# SIM868-ng.net
KiCad netlist of a schematic drawn in EAGLE
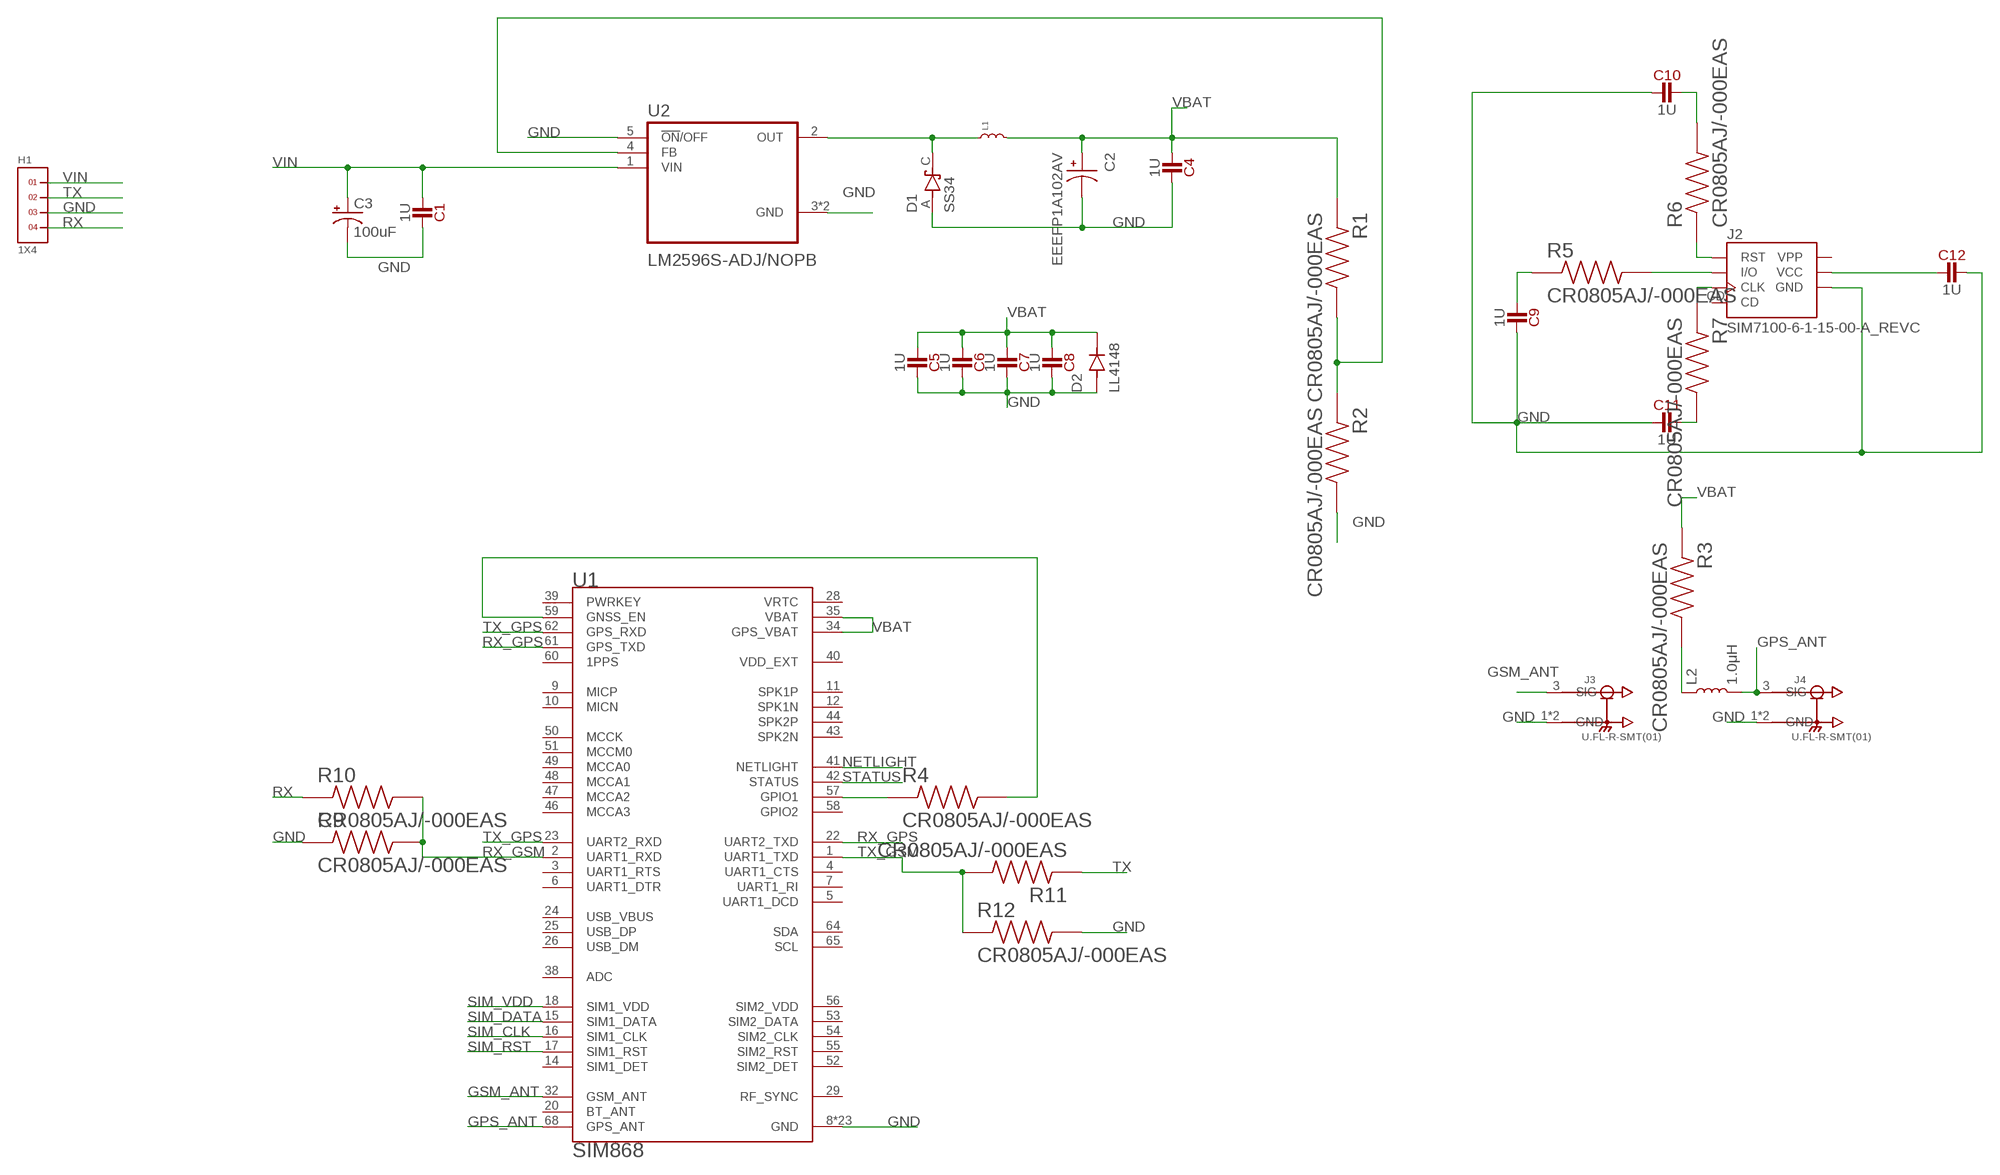
[diagram p0: schematic, sheet 1]

(export (version "E")
  (design (tool "Eeschema 10.0.6"))
  (components
    (comp (ref "C1")
      (value "1U")
      (footprint "eagle-import:C-0805")
      (libsource (lib "eagle-import") (part "?1U"))
    )
    (comp (ref "C2")
      (value "EEEFP1A102AV")
      (footprint "eagle-import:CAP_EEEFP1A102AV")
      (fields (field (name "MF") "Panasonic") (field (name "MP") "EEE-FP1A102AV"))
      (libsource (lib "eagle-import") (part "EEEFP1A102AV"))
    )
    (comp (ref "C3")
      (value "100uF")
      (footprint "eagle-import:EIA3528")
      (libsource (lib "eagle-import") (part "100UF-POLAR-EIA3528-10V-20%(TANT)"))
    )
    (comp (ref "C4")
      (value "1U")
      (footprint "eagle-import:C-0805")
      (libsource (lib "eagle-import") (part "?1U"))
    )
    (comp (ref "C5")
      (value "1U")
      (footprint "eagle-import:C-0805")
      (libsource (lib "eagle-import") (part "?1U"))
    )
    (comp (ref "C6")
      (value "1U")
      (footprint "eagle-import:C-0805")
      (libsource (lib "eagle-import") (part "?1U"))
    )
    (comp (ref "C7")
      (value "1U")
      (footprint "eagle-import:C-0805")
      (libsource (lib "eagle-import") (part "?1U"))
    )
    (comp (ref "C8")
      (value "1U")
      (footprint "eagle-import:C-0805")
      (libsource (lib "eagle-import") (part "?1U"))
    )
    (comp (ref "C9")
      (value "1U")
      (footprint "eagle-import:C-0805")
      (libsource (lib "eagle-import") (part "?1U"))
    )
    (comp (ref "C10")
      (value "1U")
      (footprint "eagle-import:C-0805")
      (libsource (lib "eagle-import") (part "?1U"))
    )
    (comp (ref "C11")
      (value "1U")
      (footprint "eagle-import:C-0805")
      (libsource (lib "eagle-import") (part "?1U"))
    )
    (comp (ref "C12")
      (value "1U")
      (footprint "eagle-import:C-0805")
      (libsource (lib "eagle-import") (part "?1U"))
    )
    (comp (ref "D1")
      (value "SS34")
      (footprint "eagle-import:DIOM7959X265N")
      (fields (field (name "MF") "ON Semiconductor"))
      (libsource (lib "eagle-import") (part "SS34"))
    )
    (comp (ref "D2")
      (value "LL4148")
      (footprint "eagle-import:DIO_LL4148")
      (fields (field (name "MF") "ON"))
      (libsource (lib "eagle-import") (part "LL4148"))
    )
    (comp (ref "H1")
      (value "1X4")
      (footprint "eagle-import:1X4")
      (libsource (lib "eagle-import") (part "1X4"))
    )
    (comp (ref "J2")
      (value "SIM7100-6-1-15-00-A_REVC")
      (footprint "eagle-import:GCT_SIM7100-6-1-15-00-A_REVC")
      (fields (field (name "MF") "Global Connector Technology") (field (name "MP") "SIM7100-6-1-15-00-A"))
      (libsource (lib "eagle-import") (part "SIM7100-6-1-15-00-A_REVC"))
    )
    (comp (ref "J3")
      (value "U.FL-R-SMT(01)")
      (footprint "eagle-import:HRS_U.FL-R-SMT(01)")
      (fields (field (name "MF") "Hirose Electric Co Ltd"))
      (libsource (lib "eagle-import") (part "U.FL-R-SMT(01)"))
    )
    (comp (ref "J4")
      (value "U.FL-R-SMT(01)")
      (footprint "eagle-import:HRS_U.FL-R-SMT(01)")
      (fields (field (name "MF") "Hirose Electric Co Ltd"))
      (libsource (lib "eagle-import") (part "U.FL-R-SMT(01)"))
    )
    (comp (ref "L1")
      (value "INDUCTOR.XAL1010")
      (footprint "eagle-import:XAL1010")
      (libsource (lib "eagle-import") (part "INDUCTOR.XAL1010"))
    )
    (comp (ref "L2")
      (value "1.0μH")
      (footprint "eagle-import:0805-WIDE")
      (libsource (lib "eagle-import") (part "1.0μH-0805_WIDE-1.0μH-1.45A-0.106OHM-1.0MM_H"))
    )
    (comp (ref "R1")
      (value "CR0805AJ/-000EAS")
      (footprint "eagle-import:RESC2012X60N")
      (fields (field (name "MF") "Bourns"))
      (libsource (lib "eagle-import") (part "CR0805AJ/-000EAS"))
    )
    (comp (ref "R2")
      (value "CR0805AJ/-000EAS")
      (footprint "eagle-import:RESC2012X60N")
      (fields (field (name "MF") "Bourns"))
      (libsource (lib "eagle-import") (part "CR0805AJ/-000EAS"))
    )
    (comp (ref "R3")
      (value "CR0805AJ/-000EAS")
      (footprint "eagle-import:RESC2012X60N")
      (fields (field (name "MF") "Bourns"))
      (libsource (lib "eagle-import") (part "CR0805AJ/-000EAS"))
    )
    (comp (ref "R4")
      (value "CR0805AJ/-000EAS")
      (footprint "eagle-import:RESC2012X60N")
      (fields (field (name "MF") "Bourns"))
      (libsource (lib "eagle-import") (part "CR0805AJ/-000EAS"))
    )
    (comp (ref "R5")
      (value "CR0805AJ/-000EAS")
      (footprint "eagle-import:RESC2012X60N")
      (fields (field (name "MF") "Bourns"))
      (libsource (lib "eagle-import") (part "CR0805AJ/-000EAS"))
    )
    (comp (ref "R6")
      (value "CR0805AJ/-000EAS")
      (footprint "eagle-import:RESC2012X60N")
      (fields (field (name "MF") "Bourns"))
      (libsource (lib "eagle-import") (part "CR0805AJ/-000EAS"))
    )
    (comp (ref "R7")
      (value "CR0805AJ/-000EAS")
      (footprint "eagle-import:RESC2012X60N")
      (fields (field (name "MF") "Bourns"))
      (libsource (lib "eagle-import") (part "CR0805AJ/-000EAS"))
    )
    (comp (ref "R9")
      (value "CR0805AJ/-000EAS")
      (footprint "eagle-import:RESC2012X60N")
      (fields (field (name "MF") "Bourns"))
      (libsource (lib "eagle-import") (part "CR0805AJ/-000EAS"))
    )
    (comp (ref "R10")
      (value "CR0805AJ/-000EAS")
      (footprint "eagle-import:RESC2012X60N")
      (fields (field (name "MF") "Bourns"))
      (libsource (lib "eagle-import") (part "CR0805AJ/-000EAS"))
    )
    (comp (ref "R11")
      (value "CR0805AJ/-000EAS")
      (footprint "eagle-import:RESC2012X60N")
      (fields (field (name "MF") "Bourns"))
      (libsource (lib "eagle-import") (part "CR0805AJ/-000EAS"))
    )
    (comp (ref "R12")
      (value "CR0805AJ/-000EAS")
      (footprint "eagle-import:RESC2012X60N")
      (fields (field (name "MF") "Bourns"))
      (libsource (lib "eagle-import") (part "CR0805AJ/-000EAS"))
    )
    (comp (ref "U1")
      (value "SIM868")
      (footprint "eagle-import:XCVR_SIM868")
      (fields (field (name "MF") "MikroElektronika"))
      (libsource (lib "eagle-import") (part "SIM868"))
    )
    (comp (ref "U2")
      (value "LM2596S-ADJ/NOPB")
      (footprint "eagle-import:VREG_LM2596S-ADJ_NOPB")
      (fields (field (name "MF") "Texas Instruments"))
      (libsource (lib "eagle-import") (part "LM2596S-ADJ/NOPB"))
    )
  )
  (nets
    (net (code "1") (name "/GND") (class "Default")
      (node (ref "C1") (pin "2") (pinfunction "2_2") (pintype "passive"))
      (node (ref "C10") (pin "1") (pinfunction "1_1") (pintype "passive"))
      (node (ref "C11") (pin "1") (pinfunction "1_1") (pintype "passive"))
      (node (ref "C12") (pin "2") (pinfunction "2_2") (pintype "passive"))
      (node (ref "C2") (pin "2") (pinfunction "2_2") (pintype "passive"))
      (node (ref "C3") (pin "C") (pinfunction "-_C") (pintype "passive"))
      (node (ref "C4") (pin "2") (pinfunction "2_2") (pintype "passive"))
      (node (ref "C5") (pin "2") (pinfunction "2_2") (pintype "passive"))
      (node (ref "C6") (pin "2") (pinfunction "2_2") (pintype "passive"))
      (node (ref "C7") (pin "2") (pinfunction "2_2") (pintype "passive"))
      (node (ref "C8") (pin "2") (pinfunction "2_2") (pintype "passive"))
      (node (ref "C9") (pin "2") (pinfunction "2_2") (pintype "passive"))
      (node (ref "D1") (pin "A") (pinfunction "A_A") (pintype "passive"))
      (node (ref "D2") (pin "A") (pinfunction "A_A") (pintype "passive"))
      (node (ref "H1") (pin "3") (pinfunction "3_3") (pintype "bidirectional"))
      (node (ref "J2") (pin "C5") (pinfunction "GND_C5") (pintype "power_in"))
      (node (ref "J3") (pin "1") (pinfunction "GND_1") (pintype "passive"))
      (node (ref "J3") (pin "2") (pinfunction "GND_2") (pintype "passive"))
      (node (ref "J4") (pin "1") (pinfunction "GND_1") (pintype "passive"))
      (node (ref "J4") (pin "2") (pinfunction "GND_2") (pintype "passive"))
      (node (ref "R12") (pin "2") (pinfunction "2_2") (pintype "passive"))
      (node (ref "R2") (pin "2") (pinfunction "2_2") (pintype "passive"))
      (node (ref "R9") (pin "1") (pinfunction "1_1") (pintype "passive"))
      (node (ref "U1") (pin "13") (pinfunction "GND_13") (pintype "power_in"))
      (node (ref "U1") (pin "19") (pinfunction "GND_19") (pintype "power_in"))
      (node (ref "U1") (pin "21") (pinfunction "GND_21") (pintype "power_in"))
      (node (ref "U1") (pin "27") (pinfunction "GND_27") (pintype "power_in"))
      (node (ref "U1") (pin "30") (pinfunction "GND_30") (pintype "power_in"))
      (node (ref "U1") (pin "31") (pinfunction "GND_31") (pintype "power_in"))
      (node (ref "U1") (pin "33") (pinfunction "GND_33") (pintype "power_in"))
      (node (ref "U1") (pin "36") (pinfunction "GND_36") (pintype "power_in"))
      (node (ref "U1") (pin "37") (pinfunction "GND_37") (pintype "power_in"))
      (node (ref "U1") (pin "45") (pinfunction "GND_45") (pintype "power_in"))
      (node (ref "U1") (pin "63") (pinfunction "GND_63") (pintype "power_in"))
      (node (ref "U1") (pin "66") (pinfunction "GND_66") (pintype "power_in"))
      (node (ref "U1") (pin "67") (pinfunction "GND_67") (pintype "power_in"))
      (node (ref "U1") (pin "69") (pinfunction "GND_69") (pintype "power_in"))
      (node (ref "U1") (pin "70") (pinfunction "GND_70") (pintype "power_in"))
      (node (ref "U1") (pin "71") (pinfunction "GND_71") (pintype "power_in"))
      (node (ref "U1") (pin "72") (pinfunction "GND_72") (pintype "power_in"))
      (node (ref "U1") (pin "73") (pinfunction "GND_73") (pintype "power_in"))
      (node (ref "U1") (pin "74") (pinfunction "GND_74") (pintype "power_in"))
      (node (ref "U1") (pin "75") (pinfunction "GND_75") (pintype "power_in"))
      (node (ref "U1") (pin "76") (pinfunction "GND_76") (pintype "power_in"))
      (node (ref "U1") (pin "77") (pinfunction "GND_77") (pintype "power_in"))
      (node (ref "U1") (pin "8") (pinfunction "GND_8") (pintype "power_in"))
      (node (ref "U2") (pin "3") (pinfunction "GND_3") (pintype "power_in"))
      (node (ref "U2") (pin "5") (pinfunction "~{ON}/OFF_5") (pintype "input"))
      (node (ref "U2") (pin "6") (pinfunction "GND_6") (pintype "power_in"))
    )
    (net (code "2") (name "/GPS_ANT") (class "Default")
      (node (ref "J4") (pin "3") (pinfunction "SIG_3") (pintype "passive"))
      (node (ref "L2") (pin "2") (pinfunction "2_2") (pintype "passive"))
      (node (ref "U1") (pin "68") (pinfunction "GPS_ANT_68") (pintype "input"))
    )
    (net (code "3") (name "/GSM_ANT") (class "Default")
      (node (ref "J3") (pin "3") (pinfunction "SIG_3") (pintype "passive"))
      (node (ref "U1") (pin "32") (pinfunction "GSM_ANT_32") (pintype "bidirectional"))
    )
    (net (code "4") (name "/NETLIGHT") (class "Default")
      (node (ref "U1") (pin "41") (pinfunction "NETLIGHT_41") (pintype "output"))
    )
    (net (code "5") (name "/RX") (class "Default")
      (node (ref "H1") (pin "4") (pinfunction "4_4") (pintype "bidirectional"))
      (node (ref "R10") (pin "1") (pinfunction "1_1") (pintype "passive"))
    )
    (net (code "6") (name "/RX_GPS") (class "Default")
      (node (ref "U1") (pin "22") (pinfunction "UART2_TXD_22") (pintype "output"))
      (node (ref "U1") (pin "61") (pinfunction "GPS_TXD_61") (pintype "output"))
    )
    (net (code "7") (name "/RX_GSM") (class "Default")
      (node (ref "R10") (pin "2") (pinfunction "2_2") (pintype "passive"))
      (node (ref "R9") (pin "2") (pinfunction "2_2") (pintype "passive"))
      (node (ref "U1") (pin "2") (pinfunction "UART1_RXD_2") (pintype "input"))
    )
    (net (code "8") (name "/SIM_CLK") (class "Default")
      (node (ref "U1") (pin "16") (pinfunction "SIM1_CLK_16") (pintype "output"))
    )
    (net (code "9") (name "/SIM_DATA") (class "Default")
      (node (ref "U1") (pin "15") (pinfunction "SIM1_DATA_15") (pintype "bidirectional"))
    )
    (net (code "10") (name "/SIM_RST") (class "Default")
      (node (ref "U1") (pin "17") (pinfunction "SIM1_RST_17") (pintype "output"))
    )
    (net (code "11") (name "/SIM_VDD") (class "Default")
      (node (ref "U1") (pin "18") (pinfunction "SIM1_VDD_18") (pintype "output"))
    )
    (net (code "12") (name "/STATUS") (class "Default")
      (node (ref "U1") (pin "42") (pinfunction "STATUS_42") (pintype "output"))
    )
    (net (code "13") (name "/TX") (class "Default")
      (node (ref "H1") (pin "2") (pinfunction "2_2") (pintype "bidirectional"))
      (node (ref "R11") (pin "1") (pinfunction "1_1") (pintype "passive"))
    )
    (net (code "14") (name "/TX_GPS") (class "Default")
      (node (ref "U1") (pin "23") (pinfunction "UART2_RXD_23") (pintype "input"))
      (node (ref "U1") (pin "62") (pinfunction "GPS_RXD_62") (pintype "input"))
    )
    (net (code "15") (name "/TX_GSM") (class "Default")
      (node (ref "R11") (pin "2") (pinfunction "2_2") (pintype "passive"))
      (node (ref "R12") (pin "1") (pinfunction "1_1") (pintype "passive"))
      (node (ref "U1") (pin "1") (pinfunction "UART1_TXD_1") (pintype "output"))
    )
    (net (code "16") (name "/VBAT") (class "Default")
      (node (ref "C2") (pin "1") (pinfunction "1_1") (pintype "passive"))
      (node (ref "C4") (pin "1") (pinfunction "1_1") (pintype "passive"))
      (node (ref "C5") (pin "1") (pinfunction "1_1") (pintype "passive"))
      (node (ref "C6") (pin "1") (pinfunction "1_1") (pintype "passive"))
      (node (ref "C7") (pin "1") (pinfunction "1_1") (pintype "passive"))
      (node (ref "C8") (pin "1") (pinfunction "1_1") (pintype "passive"))
      (node (ref "D2") (pin "C") (pinfunction "C_C") (pintype "passive"))
      (node (ref "L1") (pin "P$2") (pinfunction "2_P$2") (pintype "passive"))
      (node (ref "R1") (pin "1") (pinfunction "1_1") (pintype "passive"))
      (node (ref "R3") (pin "1") (pinfunction "1_1") (pintype "passive"))
      (node (ref "U1") (pin "34") (pinfunction "GPS_VBAT_34") (pintype "power_in"))
      (node (ref "U1") (pin "35") (pinfunction "VBAT_35") (pintype "power_in"))
    )
    (net (code "17") (name "/VIN") (class "Default")
      (node (ref "C1") (pin "1") (pinfunction "1_1") (pintype "passive"))
      (node (ref "C3") (pin "A") (pinfunction "+_A") (pintype "passive"))
      (node (ref "H1") (pin "1") (pinfunction "1_1") (pintype "bidirectional"))
      (node (ref "U2") (pin "1") (pinfunction "VIN_1") (pintype "input"))
    )
    (net (code "18") (name "/VPP") (class "Default")
      (node (ref "J2") (pin "C6") (pinfunction "VPP_C6") (pintype "power_in"))
    )
    (net (code "19") (name "/VRTC") (class "Default")
      (node (ref "U1") (pin "28") (pinfunction "VRTC_28") (pintype "power_in"))
    )
    (net (code "20") (name "Net-(C9-Pad1)") (class "Default")
      (node (ref "C9") (pin "1") (pinfunction "1_1") (pintype "passive"))
      (node (ref "R5") (pin "1") (pinfunction "1_1") (pintype "passive"))
    )
    (net (code "21") (name "Net-(C10-Pad2)") (class "Default")
      (node (ref "C10") (pin "2") (pinfunction "2_2") (pintype "passive"))
      (node (ref "R6") (pin "2") (pinfunction "2_2") (pintype "passive"))
    )
    (net (code "22") (name "Net-(C11-Pad2)") (class "Default")
      (node (ref "C11") (pin "2") (pinfunction "2_2") (pintype "passive"))
      (node (ref "R7") (pin "2") (pinfunction "2_2") (pintype "passive"))
    )
    (net (code "23") (name "Net-(D1-K)") (class "Default")
      (node (ref "D1") (pin "C") (pinfunction "K_C") (pintype "passive"))
      (node (ref "L1") (pin "P$1") (pinfunction "1_P$1") (pintype "passive"))
      (node (ref "U2") (pin "2") (pinfunction "OUT_2") (pintype "output"))
    )
    (net (code "24") (name "Net-(J2-CLK)") (class "Default")
      (node (ref "J2") (pin "C3") (pinfunction "CLK_C3") (pintype "bidirectional"))
      (node (ref "R7") (pin "1") (pinfunction "1_1") (pintype "passive"))
    )
    (net (code "25") (name "Net-(J2-I{slash}O)") (class "Default")
      (node (ref "J2") (pin "C7") (pinfunction "I/O_C7") (pintype "bidirectional"))
      (node (ref "R5") (pin "2") (pinfunction "2_2") (pintype "passive"))
    )
    (net (code "26") (name "Net-(J2-RST)") (class "Default")
      (node (ref "J2") (pin "C2") (pinfunction "RST_C2") (pintype "input"))
      (node (ref "R6") (pin "1") (pinfunction "1_1") (pintype "passive"))
    )
    (net (code "27") (name "Net-(J2-VCC)") (class "Default")
      (node (ref "C12") (pin "1") (pinfunction "1_1") (pintype "passive"))
      (node (ref "J2") (pin "C1") (pinfunction "VCC_C1") (pintype "power_in"))
    )
    (net (code "28") (name "Net-(L2-Pad1)") (class "Default")
      (node (ref "L2") (pin "1") (pinfunction "1_1") (pintype "passive"))
      (node (ref "R3") (pin "2") (pinfunction "2_2") (pintype "passive"))
    )
    (net (code "29") (name "Net-(U1-GNSS_EN)") (class "Default")
      (node (ref "R4") (pin "2") (pinfunction "2_2") (pintype "passive"))
      (node (ref "U1") (pin "59") (pinfunction "GNSS_EN_59") (pintype "input"))
    )
    (net (code "30") (name "Net-(U1-GPIO1)") (class "Default")
      (node (ref "R4") (pin "1") (pinfunction "1_1") (pintype "passive"))
      (node (ref "U1") (pin "57") (pinfunction "GPIO1_57") (pintype "bidirectional"))
    )
    (net (code "31") (name "Net-(U2-FB)") (class "Default")
      (node (ref "R1") (pin "2") (pinfunction "2_2") (pintype "passive"))
      (node (ref "R2") (pin "1") (pinfunction "1_1") (pintype "passive"))
      (node (ref "U2") (pin "4") (pinfunction "FB_4") (pintype "input"))
    )
    (net (code "32") (name "unconnected-(J2-PadCD)") (class "Default")
      (node (ref "J2") (pin "CD") (pinfunction "CD_CD") (pintype "passive"))
    )
    (net (code "33") (name "unconnected-(U1-1PPS-Pad60)") (class "Default")
      (node (ref "U1") (pin "60") (pinfunction "1PPS_60") (pintype "output"))
    )
    (net (code "34") (name "unconnected-(U1-ADC-Pad38)") (class "Default")
      (node (ref "U1") (pin "38") (pinfunction "ADC_38") (pintype "input"))
    )
    (net (code "35") (name "unconnected-(U1-BT_ANT-Pad20)") (class "Default")
      (node (ref "U1") (pin "20") (pinfunction "BT_ANT_20") (pintype "bidirectional"))
    )
    (net (code "36") (name "unconnected-(U1-GPIO2-Pad58)") (class "Default")
      (node (ref "U1") (pin "58") (pinfunction "GPIO2_58") (pintype "bidirectional"))
    )
    (net (code "37") (name "unconnected-(U1-MCCA0-Pad49)") (class "Default")
      (node (ref "U1") (pin "49") (pinfunction "MCCA0_49") (pintype "bidirectional"))
    )
    (net (code "38") (name "unconnected-(U1-MCCA1-Pad48)") (class "Default")
      (node (ref "U1") (pin "48") (pinfunction "MCCA1_48") (pintype "bidirectional"))
    )
    (net (code "39") (name "unconnected-(U1-MCCA2-Pad47)") (class "Default")
      (node (ref "U1") (pin "47") (pinfunction "MCCA2_47") (pintype "bidirectional"))
    )
    (net (code "40") (name "unconnected-(U1-MCCA3-Pad46)") (class "Default")
      (node (ref "U1") (pin "46") (pinfunction "MCCA3_46") (pintype "bidirectional"))
    )
    (net (code "41") (name "unconnected-(U1-MCCK-Pad50)") (class "Default")
      (node (ref "U1") (pin "50") (pinfunction "MCCK_50") (pintype "bidirectional"))
    )
    (net (code "42") (name "unconnected-(U1-MCCM0-Pad51)") (class "Default")
      (node (ref "U1") (pin "51") (pinfunction "MCCM0_51") (pintype "bidirectional"))
    )
    (net (code "43") (name "unconnected-(U1-MICN-Pad10)") (class "Default")
      (node (ref "U1") (pin "10") (pinfunction "MICN_10") (pintype "input"))
    )
    (net (code "44") (name "unconnected-(U1-MICP-Pad9)") (class "Default")
      (node (ref "U1") (pin "9") (pinfunction "MICP_9") (pintype "input"))
    )
    (net (code "45") (name "unconnected-(U1-PWRKEY-Pad39)") (class "Default")
      (node (ref "U1") (pin "39") (pinfunction "PWRKEY_39") (pintype "input"))
    )
    (net (code "46") (name "unconnected-(U1-RF_SYNC-Pad29)") (class "Default")
      (node (ref "U1") (pin "29") (pinfunction "RF_SYNC_29") (pintype "output"))
    )
    (net (code "47") (name "unconnected-(U1-SCL-Pad65)") (class "Default")
      (node (ref "U1") (pin "65") (pinfunction "SCL_65") (pintype "output"))
    )
    (net (code "48") (name "unconnected-(U1-SDA-Pad64)") (class "Default")
      (node (ref "U1") (pin "64") (pinfunction "SDA_64") (pintype "bidirectional"))
    )
    (net (code "49") (name "unconnected-(U1-SIM1_DET-Pad14)") (class "Default")
      (node (ref "U1") (pin "14") (pinfunction "SIM1_DET_14") (pintype "input"))
    )
    (net (code "50") (name "unconnected-(U1-SIM2_CLK-Pad54)") (class "Default")
      (node (ref "U1") (pin "54") (pinfunction "SIM2_CLK_54") (pintype "output"))
    )
    (net (code "51") (name "unconnected-(U1-SIM2_DATA-Pad53)") (class "Default")
      (node (ref "U1") (pin "53") (pinfunction "SIM2_DATA_53") (pintype "bidirectional"))
    )
    (net (code "52") (name "unconnected-(U1-SIM2_DET-Pad52)") (class "Default")
      (node (ref "U1") (pin "52") (pinfunction "SIM2_DET_52") (pintype "input"))
    )
    (net (code "53") (name "unconnected-(U1-SIM2_RST-Pad55)") (class "Default")
      (node (ref "U1") (pin "55") (pinfunction "SIM2_RST_55") (pintype "output"))
    )
    (net (code "54") (name "unconnected-(U1-SIM2_VDD-Pad56)") (class "Default")
      (node (ref "U1") (pin "56") (pinfunction "SIM2_VDD_56") (pintype "output"))
    )
    (net (code "55") (name "unconnected-(U1-SPK1N-Pad12)") (class "Default")
      (node (ref "U1") (pin "12") (pinfunction "SPK1N_12") (pintype "output"))
    )
    (net (code "56") (name "unconnected-(U1-SPK1P-Pad11)") (class "Default")
      (node (ref "U1") (pin "11") (pinfunction "SPK1P_11") (pintype "output"))
    )
    (net (code "57") (name "unconnected-(U1-SPK2N-Pad43)") (class "Default")
      (node (ref "U1") (pin "43") (pinfunction "SPK2N_43") (pintype "output"))
    )
    (net (code "58") (name "unconnected-(U1-SPK2P-Pad44)") (class "Default")
      (node (ref "U1") (pin "44") (pinfunction "SPK2P_44") (pintype "output"))
    )
    (net (code "59") (name "unconnected-(U1-UART1_CTS-Pad4)") (class "Default")
      (node (ref "U1") (pin "4") (pinfunction "UART1_CTS_4") (pintype "output"))
    )
    (net (code "60") (name "unconnected-(U1-UART1_DCD-Pad5)") (class "Default")
      (node (ref "U1") (pin "5") (pinfunction "UART1_DCD_5") (pintype "output"))
    )
    (net (code "61") (name "unconnected-(U1-UART1_DTR-Pad6)") (class "Default")
      (node (ref "U1") (pin "6") (pinfunction "UART1_DTR_6") (pintype "input"))
    )
    (net (code "62") (name "unconnected-(U1-UART1_RI-Pad7)") (class "Default")
      (node (ref "U1") (pin "7") (pinfunction "UART1_RI_7") (pintype "output"))
    )
    (net (code "63") (name "unconnected-(U1-UART1_RTS-Pad3)") (class "Default")
      (node (ref "U1") (pin "3") (pinfunction "UART1_RTS_3") (pintype "input"))
    )
    (net (code "64") (name "unconnected-(U1-USB_DM-Pad26)") (class "Default")
      (node (ref "U1") (pin "26") (pinfunction "USB_DM_26") (pintype "bidirectional"))
    )
    (net (code "65") (name "unconnected-(U1-USB_DP-Pad25)") (class "Default")
      (node (ref "U1") (pin "25") (pinfunction "USB_DP_25") (pintype "bidirectional"))
    )
    (net (code "66") (name "unconnected-(U1-USB_VBUS-Pad24)") (class "Default")
      (node (ref "U1") (pin "24") (pinfunction "USB_VBUS_24") (pintype "input"))
    )
    (net (code "67") (name "unconnected-(U1-VDD_EXT-Pad40)") (class "Default")
      (node (ref "U1") (pin "40") (pinfunction "VDD_EXT_40") (pintype "output"))
    )
  )
)
